# Top.net
KiCad netlist of a schematic drawn in Altium Designer
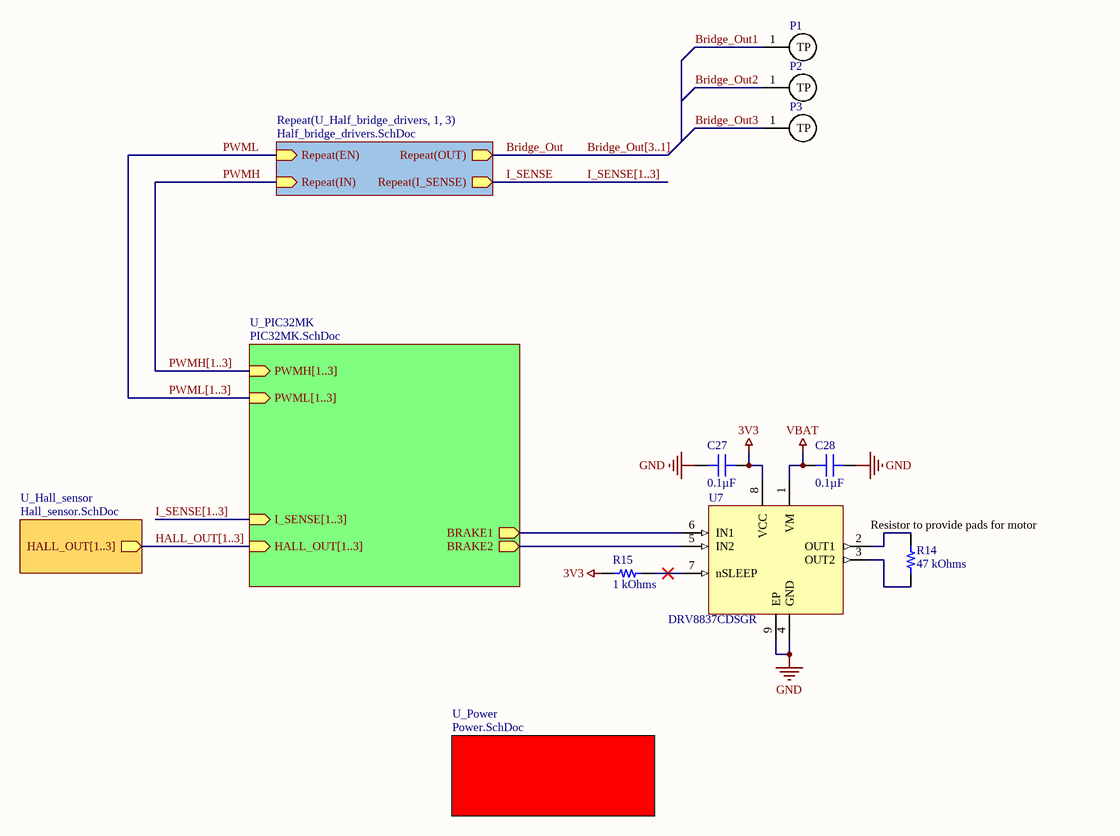
[diagram p0: Top.SchDoc]

(export (version "E")
  (design (tool "Eeschema 10.0.6"))
  (components
    (comp (ref "C27")
      (value "0.1µF")
      (footprint "CAP 0603_1608")
      (description "CAP CER 0.1UF 100V 0603 EPOXY")
      (fields
        (field (name "PART NUMBER") "GCG188R92A104KA03D")
        (field (name "MANUFACTURER") "Murata Electronics")
      )
      (libsource (lib "Celestial Altium Library - altium_library") (part "Capacitor"))
    )
    (comp (ref "C28")
      (value "0.1µF")
      (footprint "CAP 0603_1608")
      (description "CAP CER 0.1UF 100V 0603 EPOXY")
      (fields
        (field (name "PART NUMBER") "GCG188R92A104KA03D")
        (field (name "MANUFACTURER") "Murata Electronics")
      )
      (libsource (lib "Celestial Altium Library - altium_library") (part "Capacitor"))
    )
    (comp (ref "P1") (value "TP") (footprint "2mmHole") (libsource (lib "IC") (part "TP")))
    (comp (ref "P2") (value "TP") (footprint "2mmHole") (libsource (lib "IC") (part "TP")))
    (comp (ref "P3") (value "TP") (footprint "2mmHole") (libsource (lib "IC") (part "TP")))
    (comp (ref "R14")
      (value "47 kOhms")
      (footprint "RES 2512_6432")
      (description "RES 47K OHM 5% 1W 2512")
      (fields
        (field (name "PART NUMBER") "RK73B3ATTE473J")
        (field (name "MANUFACTURER") "KOA Speer Electronics, Inc.")
      )
      (libsource (lib "Celestial Altium Library - altium_library") (part "Resistor"))
    )
    (comp (ref "R15")
      (value "1 kOhms")
      (footprint "RES 0603_1608")
      (description "RES SMD 1K OHM 1% 1/10W 0603")
      (fields (field (name "PART NUMBER") "RT0603FRE071KL") (field (name "MANUFACTURER") "Yageo"))
      (libsource (lib "Celestial Altium Library - altium_library") (part "Resistor"))
    )
    (comp (ref "U7")
      (value "DRV8837CDSGR")
      (footprint "SON50P200X200X80-9N")
      (description "11-V, 1-A H-bridge motor driver 8-WSON -40 to 85")
      (fields (field (name "MF") "Texas Instruments"))
      (libsource (lib "IC") (part "DRV8837CDSGR"))
    )
  )
  (nets
    (net (code "13") (name "/BRAKE1") (class "Default")
      (node (ref "U7") (pin "6") (pinfunction "IN1_6") (pintype "input"))
    )
    (net (code "14") (name "/BRAKE2") (class "Default")
      (node (ref "U7") (pin "5") (pinfunction "IN2_5") (pintype "input"))
    )
    (net (code "16") (name "/Bridge_Out1") (class "Default")
      (node (ref "P1") (pin "1") (pinfunction "TP_1") (pintype "passive"))
    )
    (net (code "17") (name "/Bridge_Out2") (class "Default")
      (node (ref "P2") (pin "1") (pinfunction "TP_1") (pintype "passive"))
    )
    (net (code "18") (name "/Bridge_Out3") (class "Default")
      (node (ref "P3") (pin "1") (pinfunction "TP_1") (pintype "passive"))
    )
    (net (code "27") (name "3V3") (class "Default")
      (node (ref "C27") (pin "2") (pinfunction "2_2") (pintype "passive"))
      (node (ref "R15") (pin "2") (pinfunction "2_2") (pintype "passive"))
      (node (ref "U7") (pin "8") (pinfunction "VCC_8") (pintype "power_in"))
    )
    (net (code "28") (name "GND") (class "Default")
      (node (ref "C27") (pin "1") (pinfunction "1_1") (pintype "passive"))
      (node (ref "C28") (pin "2") (pinfunction "2_2") (pintype "passive"))
      (node (ref "U7") (pin "4") (pinfunction "GND_4") (pintype "power_in"))
      (node (ref "U7") (pin "9") (pinfunction "EP_9") (pintype "power_in"))
    )
    (net (code "29") (name "Net-(U7-OUT1)") (class "Default")
      (node (ref "R14") (pin "1") (pinfunction "1_1") (pintype "passive"))
      (node (ref "U7") (pin "2") (pinfunction "OUT1_2") (pintype "output"))
    )
    (net (code "30") (name "Net-(U7-OUT2)") (class "Default")
      (node (ref "R14") (pin "2") (pinfunction "2_2") (pintype "passive"))
      (node (ref "U7") (pin "3") (pinfunction "OUT2_3") (pintype "output"))
    )
    (net (code "31") (name "Net-(U7-nSLEEP)") (class "Default")
      (node (ref "R15") (pin "1") (pinfunction "1_1") (pintype "passive"))
      (node (ref "U7") (pin "7") (pinfunction "nSLEEP_7") (pintype "input"))
    )
    (net (code "32") (name "VBAT") (class "Default")
      (node (ref "C28") (pin "1") (pinfunction "1_1") (pintype "passive"))
      (node (ref "U7") (pin "1") (pinfunction "VM_1") (pintype "power_in"))
    )
  )
)
